# BMS_breakout_2.net
KiCad netlist of a schematic drawn in EAGLE
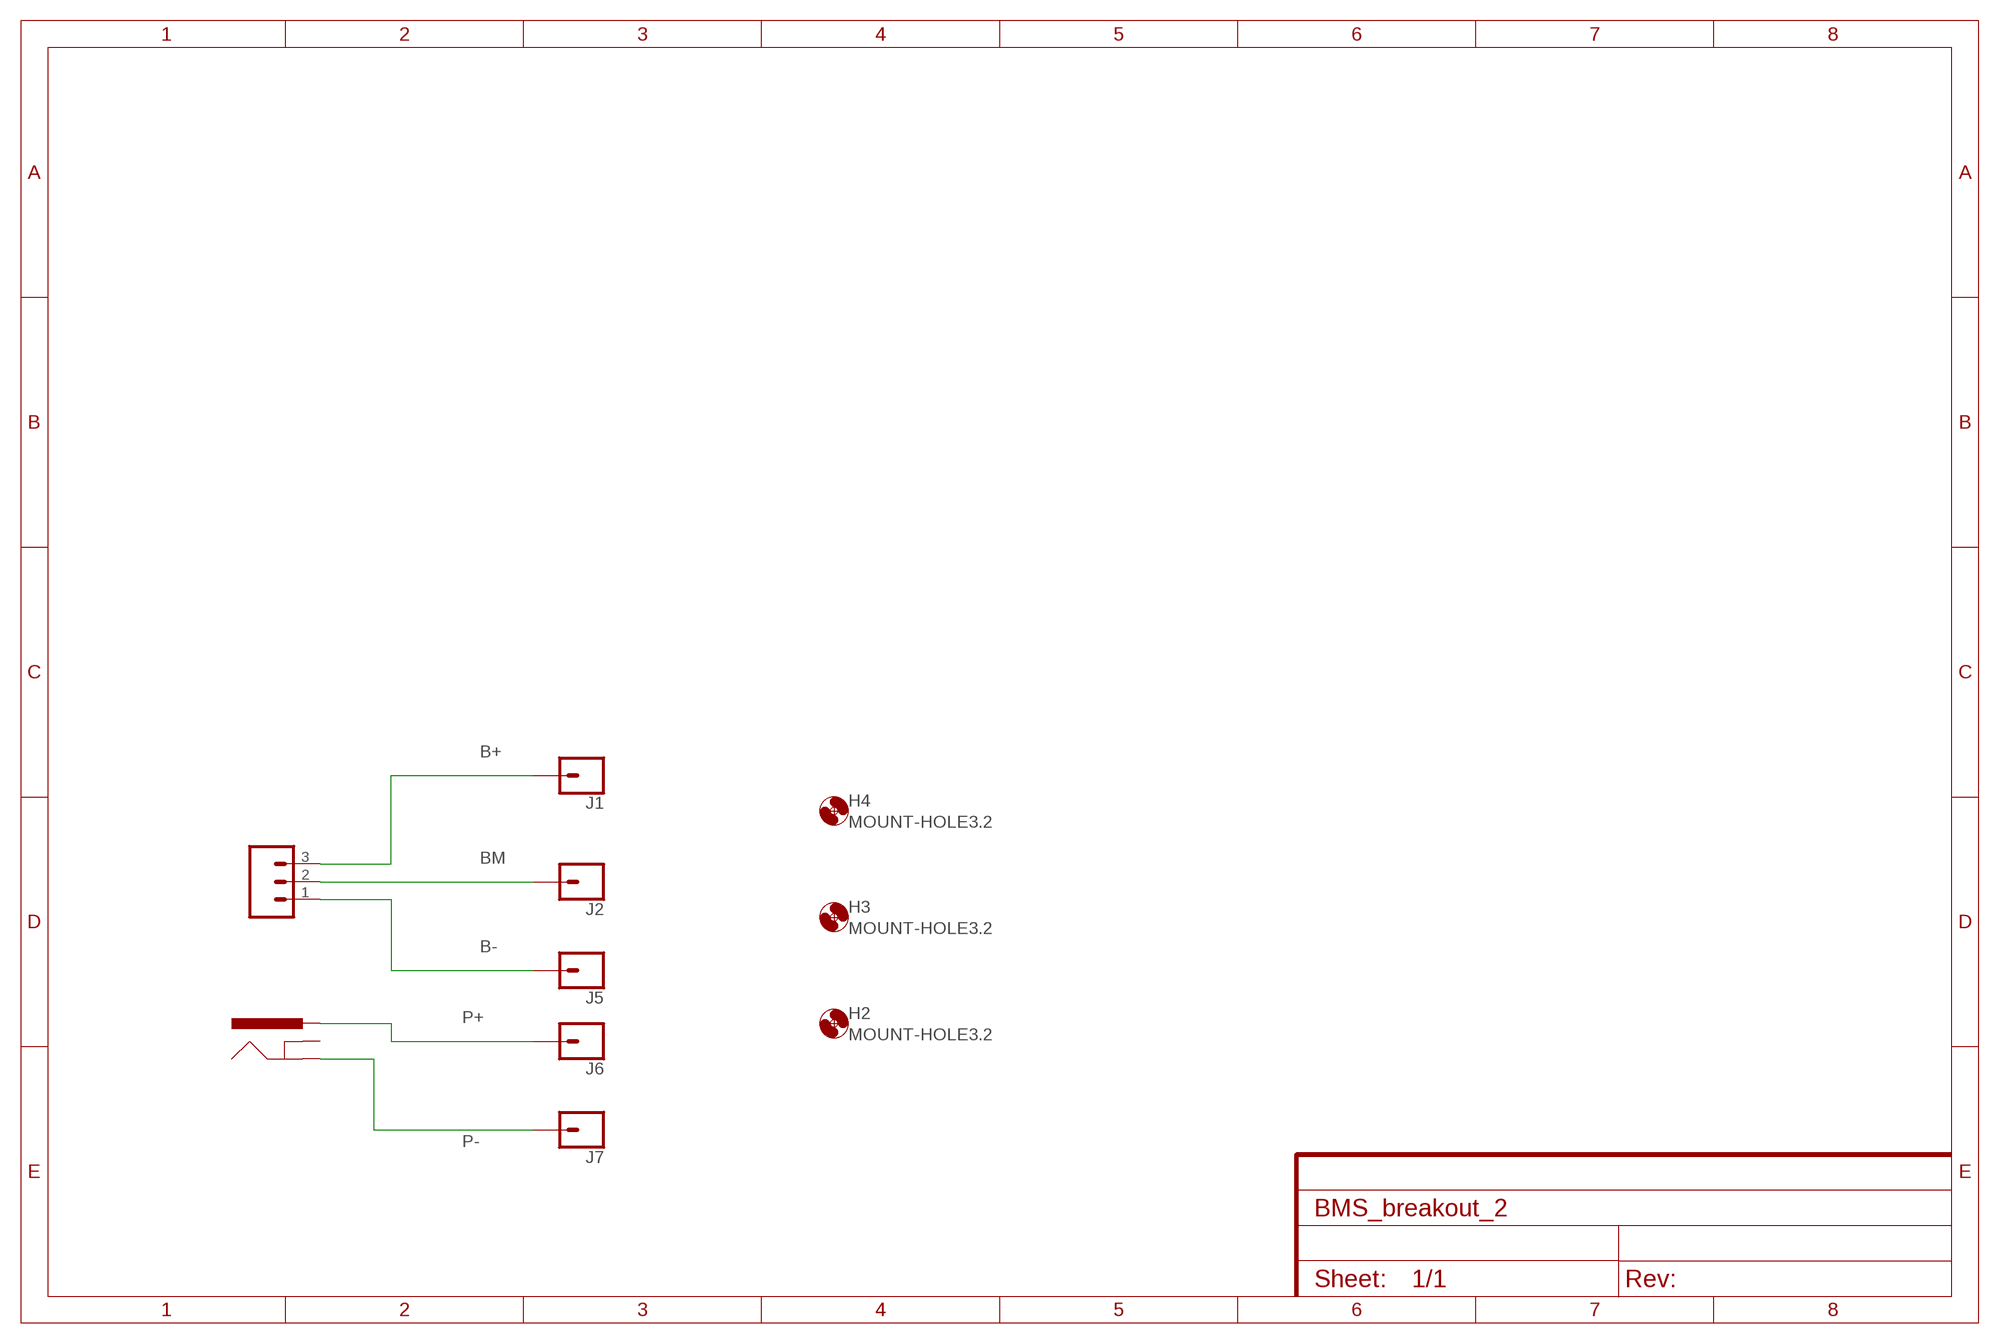
[diagram p0: schematic, sheet 1]

(export (version "E")
  (design (tool "Eeschema 10.0.6"))
  (components
    (comp (ref "H2")
      (value "MOUNT-HOLE3.2")
      (footprint "eagle-import:3,2")
      (libsource (lib "eagle-import") (part "MOUNT-HOLE3.2"))
    )
    (comp (ref "H3")
      (value "MOUNT-HOLE3.2")
      (footprint "eagle-import:3,2")
      (libsource (lib "eagle-import") (part "MOUNT-HOLE3.2"))
    )
    (comp (ref "H4")
      (value "MOUNT-HOLE3.2")
      (footprint "eagle-import:3,2")
      (libsource (lib "eagle-import") (part "MOUNT-HOLE3.2"))
    )
    (comp (ref "J1")
      (value "CONN_01")
      (footprint "eagle-import:1X01")
      (libsource (lib "eagle-import") (part "CONN_01"))
    )
    (comp (ref "J2")
      (value "CONN_01")
      (footprint "eagle-import:1X01")
      (libsource (lib "eagle-import") (part "CONN_01"))
    )
    (comp (ref "J3")
      (value "CONN_03-SCREW-5MM")
      (footprint "eagle-import:SCREWTERMINAL-5MM-3")
      (libsource (lib "eagle-import") (part "CONN_03-SCREW-5MM"))
    )
    (comp (ref "J4")
      (value "5.5x2.1mm Barrel")
      (footprint "eagle-import:POWER_JACK_SMD")
      (libsource (lib "eagle-import") (part "POWER_JACKSMD"))
    )
    (comp (ref "J5")
      (value "CONN_01")
      (footprint "eagle-import:1X01")
      (libsource (lib "eagle-import") (part "CONN_01"))
    )
    (comp (ref "J6")
      (value "CONN_01")
      (footprint "eagle-import:1X01")
      (libsource (lib "eagle-import") (part "CONN_01"))
    )
    (comp (ref "J7")
      (value "CONN_01")
      (footprint "eagle-import:1X01")
      (libsource (lib "eagle-import") (part "CONN_01"))
    )
  )
  (nets
    (net (code "1") (name "/B+") (class "Default")
      (node (ref "J1") (pin "1") (pinfunction "1_1") (pintype "passive"))
      (node (ref "J3") (pin "3") (pinfunction "3_3") (pintype "passive"))
    )
    (net (code "2") (name "/B-") (class "Default")
      (node (ref "J3") (pin "1") (pinfunction "1_1") (pintype "passive"))
      (node (ref "J5") (pin "1") (pinfunction "1_1") (pintype "passive"))
    )
    (net (code "3") (name "/BM") (class "Default")
      (node (ref "J2") (pin "1") (pinfunction "1_1") (pintype "passive"))
      (node (ref "J3") (pin "2") (pinfunction "2_2") (pintype "passive"))
    )
    (net (code "4") (name "/P+") (class "Default")
      (node (ref "J4") (pin "VIN0") (pinfunction "PWR_VIN0") (pintype "bidirectional"))
      (node (ref "J6") (pin "1") (pinfunction "1_1") (pintype "passive"))
    )
    (net (code "5") (name "/P-") (class "Default")
      (node (ref "J4") (pin "P$4") (pinfunction "GND_P$4") (pintype "bidirectional"))
      (node (ref "J7") (pin "1") (pinfunction "1_1") (pintype "passive"))
    )
    (net (code "6") (name "unconnected-(J4-GNDBREAK-PadGND)") (class "Default")
      (node (ref "J4") (pin "GND") (pinfunction "GNDBREAK_GND") (pintype "bidirectional"))
    )
  )
)
